# Drivers.net
KiCad netlist of a schematic drawn in Altium Designer
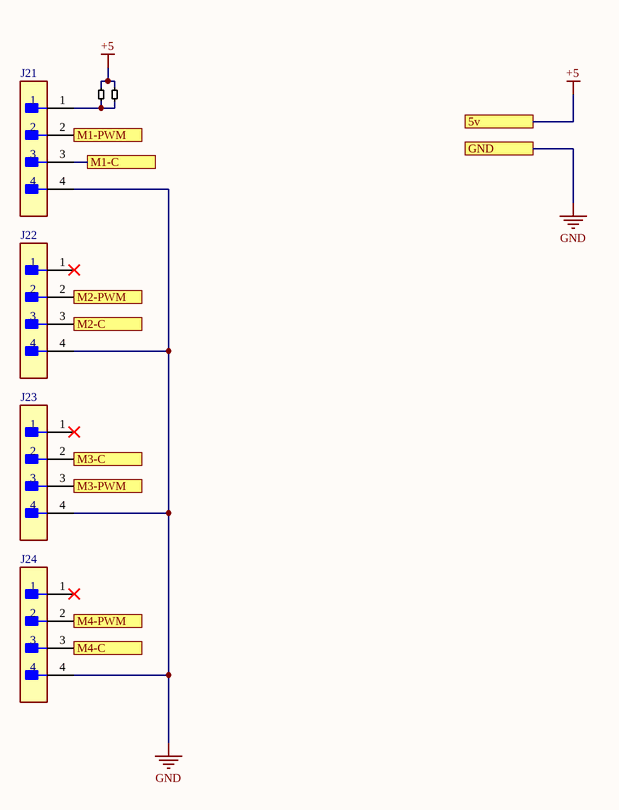
[diagram p0: Drivers.SchDoc]

(export (version "E")
  (design (tool "Eeschema 10.0.6"))
  (components
    (comp (ref "J21")
      (value "B4B-XH-A(LF)(SN)")
      (footprint "FP-B4B-XH-A_LF_SN-MFG")
      (description "CONN HEADER VERT 4POS 2.5MM")
      (libsource (lib "Altium Content Vault") (part "299a8cea1bdcbc3624fe62c390fa72c"))
    )
    (comp (ref "J22")
      (value "B4B-XH-A(LF)(SN)")
      (footprint "FP-B4B-XH-A_LF_SN-MFG")
      (description "CONN HEADER VERT 4POS 2.5MM")
      (libsource (lib "Altium Content Vault") (part "299a8cea1bdcbc3624fe62c390fa72c"))
    )
    (comp (ref "J23")
      (value "B4B-XH-A(LF)(SN)")
      (footprint "FP-B4B-XH-A_LF_SN-MFG")
      (description "CONN HEADER VERT 4POS 2.5MM")
      (libsource (lib "Altium Content Vault") (part "299a8cea1bdcbc3624fe62c390fa72c"))
    )
    (comp (ref "J24")
      (value "B4B-XH-A(LF)(SN)")
      (footprint "FP-B4B-XH-A_LF_SN-MFG")
      (description "CONN HEADER VERT 4POS 2.5MM")
      (libsource (lib "Altium Content Vault") (part "299a8cea1bdcbc3624fe62c390fa72c"))
    )
    (comp (ref "W28") (value "Jumper") (footprint "Jumper Mid") (libsource (lib "Schlib1") (part "Jumper")))
    (comp (ref "W29") (value "Jumper") (footprint "Jumper Mid") (libsource (lib "Schlib1") (part "Jumper")))
  )
  (nets
    (net (code "1") (name "+5") (class "Default")
      (node (ref "W28") (pin "2") (pinfunction "2_2") (pintype "passive"))
      (node (ref "W29") (pin "2") (pinfunction "2_2") (pintype "passive"))
    )
    (net (code "2") (name "/M1-C") (class "Default")
      (node (ref "J21") (pin "3") (pinfunction "3_3") (pintype "passive"))
    )
    (net (code "3") (name "/M1-PWM") (class "Default")
      (node (ref "J21") (pin "2") (pinfunction "2_2") (pintype "passive"))
    )
    (net (code "4") (name "/M2-C") (class "Default")
      (node (ref "J22") (pin "3") (pinfunction "3_3") (pintype "passive"))
    )
    (net (code "5") (name "/M2-PWM") (class "Default")
      (node (ref "J22") (pin "2") (pinfunction "2_2") (pintype "passive"))
    )
    (net (code "6") (name "/M3-C") (class "Default")
      (node (ref "J23") (pin "2") (pinfunction "2_2") (pintype "passive"))
    )
    (net (code "7") (name "/M3-PWM") (class "Default")
      (node (ref "J23") (pin "3") (pinfunction "3_3") (pintype "passive"))
    )
    (net (code "8") (name "/M4-C") (class "Default")
      (node (ref "J24") (pin "3") (pinfunction "3_3") (pintype "passive"))
    )
    (net (code "9") (name "/M4-PWM") (class "Default")
      (node (ref "J24") (pin "2") (pinfunction "2_2") (pintype "passive"))
    )
    (net (code "10") (name "GND") (class "Default")
      (node (ref "J21") (pin "4") (pinfunction "4_4") (pintype "passive"))
      (node (ref "J22") (pin "4") (pinfunction "4_4") (pintype "passive"))
      (node (ref "J23") (pin "4") (pinfunction "4_4") (pintype "passive"))
      (node (ref "J24") (pin "4") (pinfunction "4_4") (pintype "passive"))
    )
    (net (code "11") (name "Net-(J21-Pad1)") (class "Default")
      (node (ref "J21") (pin "1") (pinfunction "1_1") (pintype "passive"))
      (node (ref "W28") (pin "1") (pinfunction "1_1") (pintype "passive"))
      (node (ref "W29") (pin "1") (pinfunction "1_1") (pintype "passive"))
    )
    (net (code "12") (name "unconnected-(J22-Pad1)") (class "Default")
      (node (ref "J22") (pin "1") (pinfunction "1_1") (pintype "passive+no_connect"))
    )
    (net (code "13") (name "unconnected-(J23-Pad1)") (class "Default")
      (node (ref "J23") (pin "1") (pinfunction "1_1") (pintype "passive+no_connect"))
    )
    (net (code "14") (name "unconnected-(J24-Pad1)") (class "Default")
      (node (ref "J24") (pin "1") (pinfunction "1_1") (pintype "passive+no_connect"))
    )
  )
)
